# NRF_Gyro.net
KiCad netlist of a schematic drawn in Altium Designer
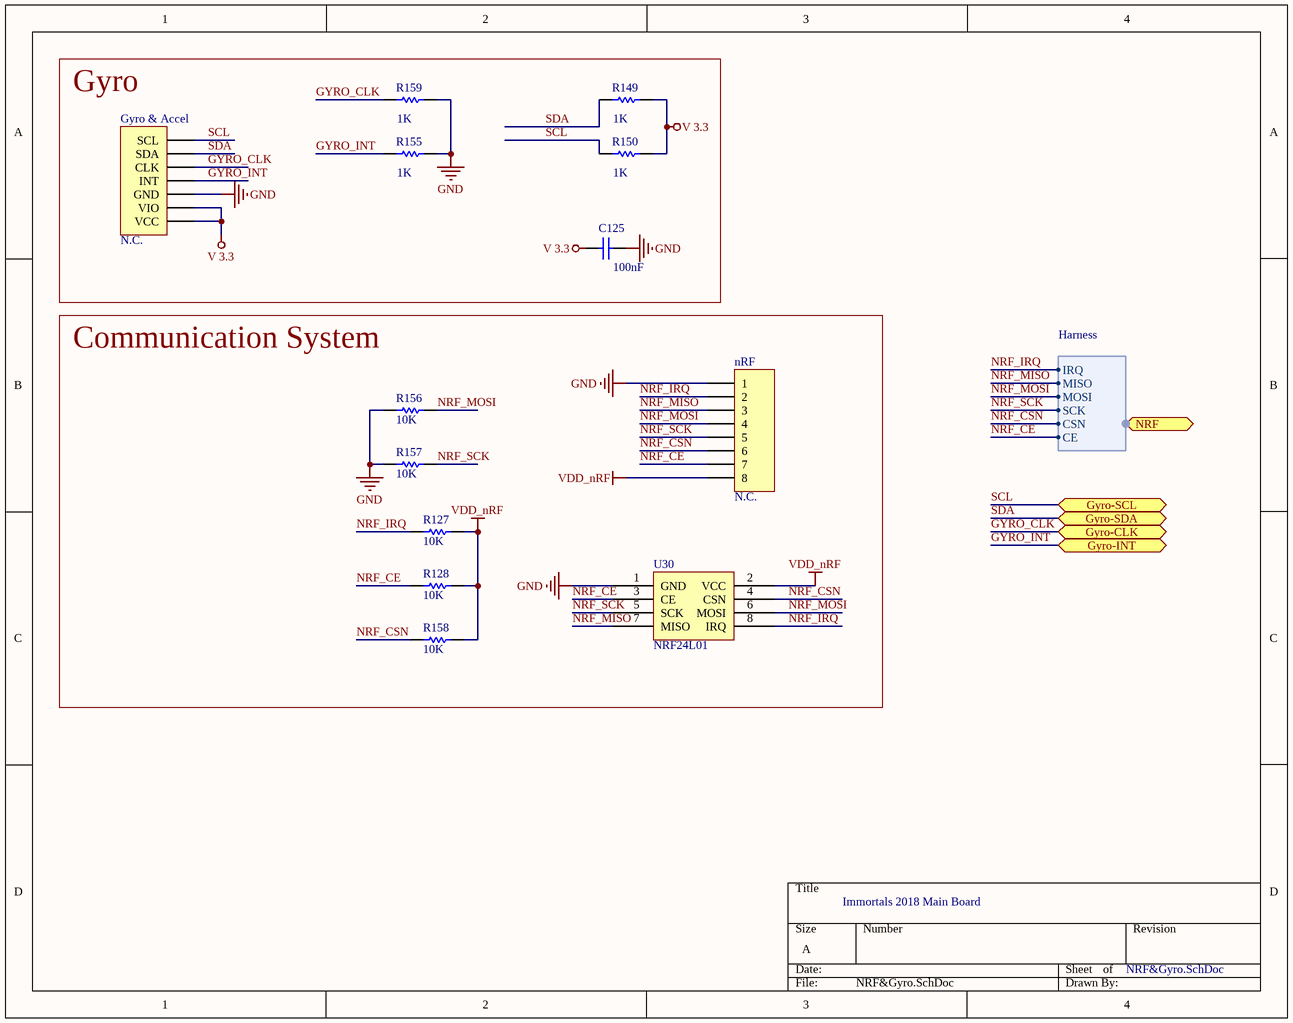
[diagram p0: NRF&Gyro.SchDoc]

(export (version "E")
  (design (tool "Eeschema 10.0.6"))
  (components
    (comp (ref "C125")
      (value "100nF")
      (footprint "C1206")
      (description "Capacitor")
      (fields (field (name "Comment") "Cap 100nF 1206"))
      (libsource (lib "Altium Nanoboard Project") (part "CAP"))
    )
    (comp (ref "Gyro & Accel")
      (value "N.C.")
      (footprint "Gyro_7pin")
      (description "Comp & Gyro")
      (libsource (lib "REV(5)") (part "Gyroscope"))
    )
    (comp (ref "nRF")
      (value "N.C.")
      (footprint "HDR1X8")
      (description "Header, 8-Pin")
      (fields (field (name "PUBLISHER") "Altium Limited"))
      (libsource (lib "Miscellaneous Connectors") (part "Header 8"))
    )
    (comp (ref "R127")
      (value "10K")
      (footprint "1608[0603]")
      (description "Semiconductor Resistor")
      (fields (field (name "Comment") "Res 10K 0603") (field (name "PUBLISHER") "Altium Limited"))
      (libsource (lib "Miscellaneous Devices") (part "Res Semi"))
    )
    (comp (ref "R128")
      (value "10K")
      (footprint "1608[0603]")
      (description "Semiconductor Resistor")
      (fields (field (name "Comment") "Res 10K 0603") (field (name "PUBLISHER") "Altium Limited"))
      (libsource (lib "Miscellaneous Devices") (part "Res Semi"))
    )
    (comp (ref "R149")
      (value "1K")
      (footprint "1608[0603]")
      (description "Semiconductor Resistor")
      (fields (field (name "Comment") "Res 1K 0603") (field (name "PUBLISHER") "Altium Limited"))
      (libsource (lib "Miscellaneous Devices") (part "Res Semi"))
    )
    (comp (ref "R150")
      (value "1K")
      (footprint "1608[0603]")
      (description "Semiconductor Resistor")
      (fields (field (name "Comment") "Res 1K 0603") (field (name "PUBLISHER") "Altium Limited"))
      (libsource (lib "Miscellaneous Devices") (part "Res Semi"))
    )
    (comp (ref "R155")
      (value "1K")
      (footprint "1608[0603]")
      (description "Semiconductor Resistor")
      (fields (field (name "Comment") "Res 1K 0603") (field (name "PUBLISHER") "Altium Limited"))
      (libsource (lib "Miscellaneous Devices") (part "Res Semi"))
    )
    (comp (ref "R156")
      (value "10K")
      (footprint "1608[0603]")
      (description "Semiconductor Resistor")
      (fields (field (name "Comment") "Res 10K 0603") (field (name "PUBLISHER") "Altium Limited"))
      (libsource (lib "Miscellaneous Devices") (part "Res Semi"))
    )
    (comp (ref "R157")
      (value "10K")
      (footprint "1608[0603]")
      (description "Semiconductor Resistor")
      (fields (field (name "Comment") "Res 10K 0603") (field (name "PUBLISHER") "Altium Limited"))
      (libsource (lib "Miscellaneous Devices") (part "Res Semi"))
    )
    (comp (ref "R158")
      (value "10K")
      (footprint "1608[0603]")
      (description "Semiconductor Resistor")
      (fields (field (name "Comment") "Res 10K 0603") (field (name "PUBLISHER") "Altium Limited"))
      (libsource (lib "Miscellaneous Devices") (part "Res Semi"))
    )
    (comp (ref "R159")
      (value "1K")
      (footprint "1608[0603]")
      (description "Semiconductor Resistor")
      (fields (field (name "Comment") "Res 1K 0603") (field (name "PUBLISHER") "Altium Limited"))
      (libsource (lib "Miscellaneous Devices") (part "Res Semi"))
    )
    (comp (ref "U30") (value "NRF24L01") (footprint "NRF24L01") (libsource (lib "REV(5)") (part "NRF24L01")))
  )
  (nets
    (net (code "2") (name "/GYRO_CLK") (class "Default")
      (node (ref "Gyro & Accel") (pin "3") (pinfunction "CLK_3") (pintype "passive"))
      (node (ref "R159") (pin "1") (pinfunction "1_1") (pintype "passive"))
    )
    (net (code "3") (name "/GYRO_INT") (class "Default")
      (node (ref "Gyro & Accel") (pin "4") (pinfunction "INT_4") (pintype "passive"))
      (node (ref "R155") (pin "1") (pinfunction "1_1") (pintype "passive"))
    )
    (net (code "4") (name "/NRF_CE") (class "Default")
      (node (ref "R128") (pin "2") (pinfunction "2_2") (pintype "passive"))
      (node (ref "U30") (pin "3") (pinfunction "CE_3") (pintype "passive"))
      (node (ref "nRF") (pin "7") (pinfunction "7_7") (pintype "passive"))
    )
    (net (code "5") (name "/NRF_CSN") (class "Default")
      (node (ref "R158") (pin "2") (pinfunction "2_2") (pintype "passive"))
      (node (ref "U30") (pin "4") (pinfunction "CSN_4") (pintype "passive"))
      (node (ref "nRF") (pin "6") (pinfunction "6_6") (pintype "passive"))
    )
    (net (code "6") (name "/NRF_IRQ") (class "Default")
      (node (ref "R127") (pin "2") (pinfunction "2_2") (pintype "passive"))
      (node (ref "U30") (pin "8") (pinfunction "IRQ_8") (pintype "passive"))
      (node (ref "nRF") (pin "2") (pinfunction "2_2") (pintype "passive"))
    )
    (net (code "7") (name "/NRF_MISO") (class "Default")
      (node (ref "U30") (pin "7") (pinfunction "MISO_7") (pintype "passive"))
      (node (ref "nRF") (pin "3") (pinfunction "3_3") (pintype "passive"))
    )
    (net (code "8") (name "/NRF_MOSI") (class "Default")
      (node (ref "R156") (pin "1") (pinfunction "1_1") (pintype "passive"))
      (node (ref "U30") (pin "6") (pinfunction "MOSI_6") (pintype "passive"))
      (node (ref "nRF") (pin "4") (pinfunction "4_4") (pintype "passive"))
    )
    (net (code "9") (name "/NRF_SCK") (class "Default")
      (node (ref "R157") (pin "1") (pinfunction "1_1") (pintype "passive"))
      (node (ref "U30") (pin "5") (pinfunction "SCK_5") (pintype "passive"))
      (node (ref "nRF") (pin "5") (pinfunction "5_5") (pintype "passive"))
    )
    (net (code "10") (name "/SCL") (class "Default")
      (node (ref "Gyro & Accel") (pin "1") (pinfunction "SCL_1") (pintype "passive"))
      (node (ref "R150") (pin "2") (pinfunction "2_2") (pintype "passive"))
    )
    (net (code "11") (name "/SDA") (class "Default")
      (node (ref "Gyro & Accel") (pin "2") (pinfunction "SDA_2") (pintype "passive"))
      (node (ref "R149") (pin "2") (pinfunction "2_2") (pintype "passive"))
    )
    (net (code "13") (name "GND") (class "Default")
      (node (ref "C125") (pin "2") (pinfunction "2_2") (pintype "passive"))
      (node (ref "Gyro & Accel") (pin "5") (pinfunction "GND_5") (pintype "passive"))
      (node (ref "R155") (pin "2") (pinfunction "2_2") (pintype "passive"))
      (node (ref "R156") (pin "2") (pinfunction "2_2") (pintype "passive"))
      (node (ref "R157") (pin "2") (pinfunction "2_2") (pintype "passive"))
      (node (ref "R159") (pin "2") (pinfunction "2_2") (pintype "passive"))
      (node (ref "U30") (pin "1") (pinfunction "GND_1") (pintype "passive"))
      (node (ref "nRF") (pin "1") (pinfunction "1_1") (pintype "passive"))
    )
    (net (code "14") (name "V 3.3") (class "Default")
      (node (ref "C125") (pin "1") (pinfunction "1_1") (pintype "passive"))
      (node (ref "Gyro & Accel") (pin "6") (pinfunction "VIO_6") (pintype "passive"))
      (node (ref "Gyro & Accel") (pin "7") (pinfunction "VCC_7") (pintype "passive"))
      (node (ref "R149") (pin "1") (pinfunction "1_1") (pintype "passive"))
      (node (ref "R150") (pin "1") (pinfunction "1_1") (pintype "passive"))
    )
    (net (code "15") (name "VDD_nRF") (class "Default")
      (node (ref "R127") (pin "1") (pinfunction "1_1") (pintype "passive"))
      (node (ref "R128") (pin "1") (pinfunction "1_1") (pintype "passive"))
      (node (ref "R158") (pin "1") (pinfunction "1_1") (pintype "passive"))
      (node (ref "U30") (pin "2") (pinfunction "VCC_2") (pintype "passive"))
      (node (ref "nRF") (pin "8") (pinfunction "8_8") (pintype "passive"))
    )
  )
)
